# 2_Power.net
KiCad netlist of a schematic drawn in Altium Designer
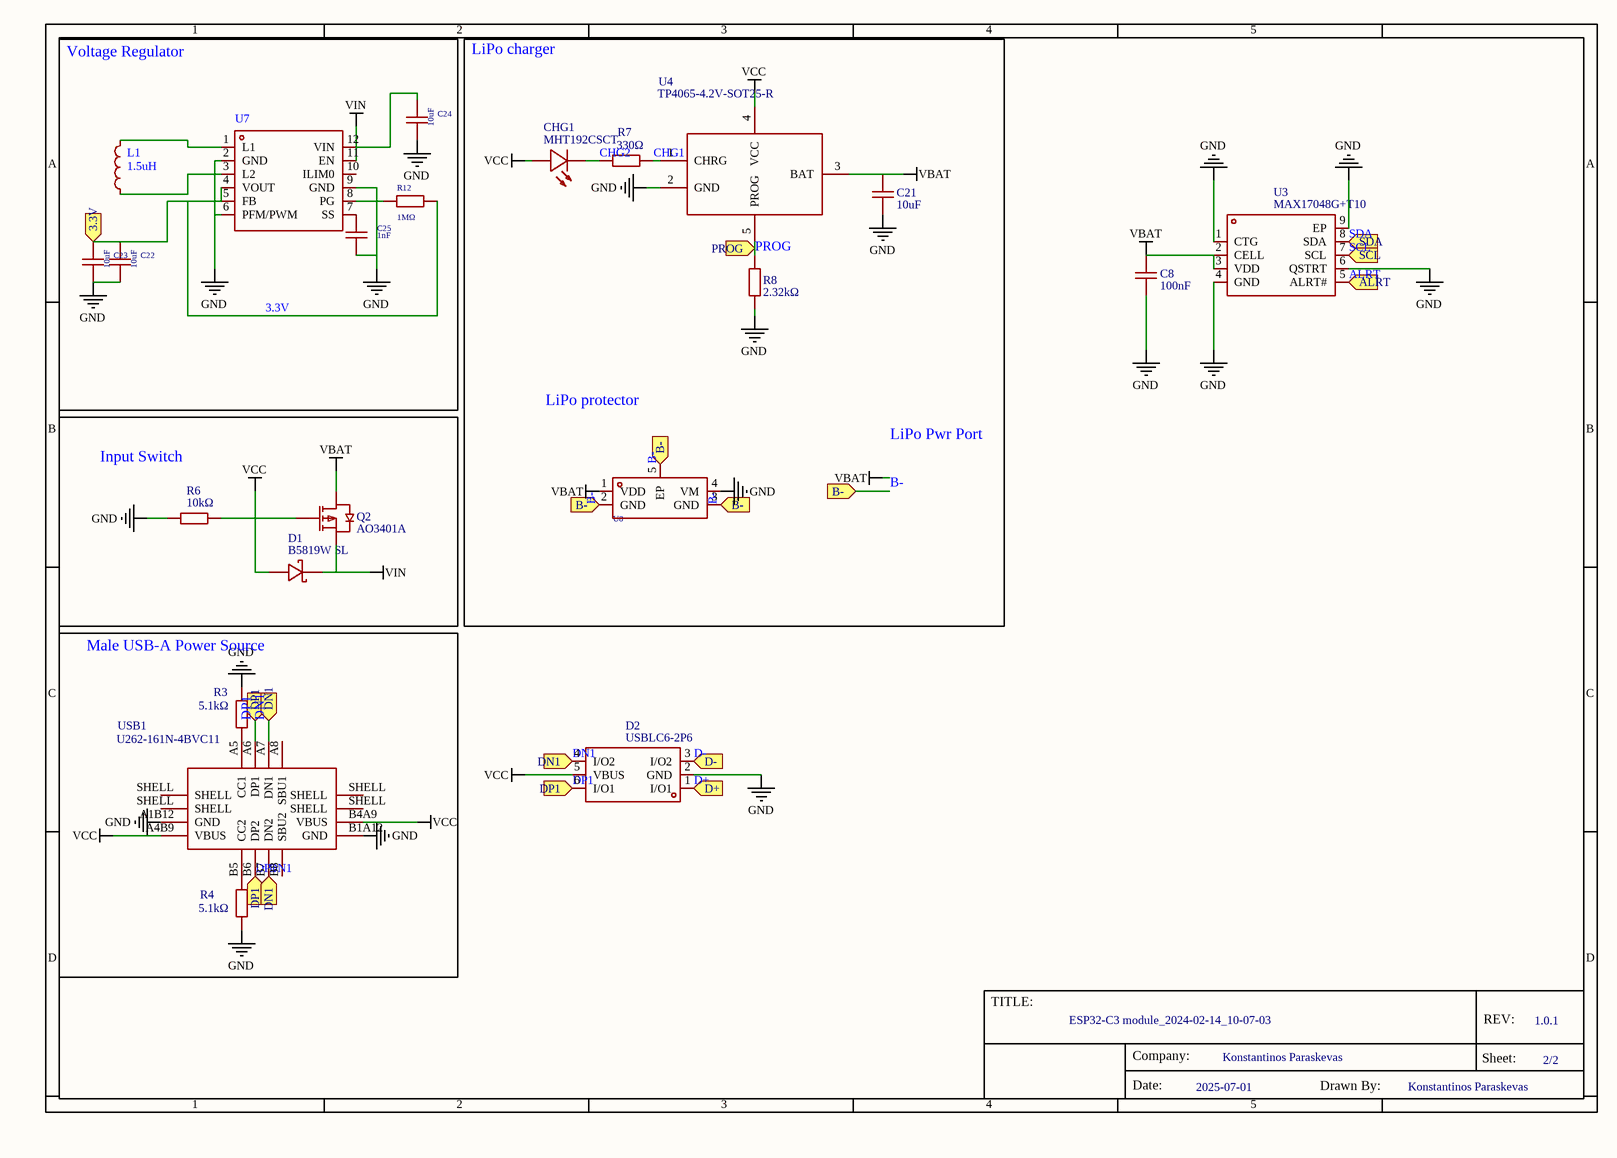
[diagram p0: 2_Power.schdoc]

(export (version "E")
  (design (tool "Eeschema 10.0.6"))
  (components
    (comp (ref "C8")
      (value "100nF")
      (footprint "C0402")
      (fields
        (field (name "MANUFACTURER") "FH(风华)")
        (field (name "MANUFACTURER PART") "0402B104K160NT")
        (field (name "TOLERANCE") "±10%")
      )
      (libsource (lib "altium-import") (part "root_1_0402B104K160NT_"))
    )
    (comp (ref "C21")
      (value "10uF")
      (footprint "C0402")
      (fields
        (field (name "MANUFACTURER") "SAMSUNG(三星)")
        (field (name "MANUFACTURER PART") "CL05A106MQ5NUNC")
        (field (name "TOLERANCE") "±20%")
      )
      (libsource (lib "altium-import") (part "root_1_CL05A106MQ5NUNC_"))
    )
    (comp (ref "C22")
      (value "10uF")
      (footprint "C0402")
      (fields
        (field (name "MANUFACTURER PART") "CL05A106MQ5NUNC")
        (field (name "MANUFACTURER") "SAMSUNG(三星)")
        (field (name "ALTIUM_VALUE") "10uF")
        (field (name "TOLERANCE") "±20%")
      )
      (libsource (lib "altium-import") (part "root_1_CL05A106MQ5NUNC_"))
    )
    (comp (ref "C23")
      (value "10uF")
      (footprint "C0402")
      (fields
        (field (name "MANUFACTURER PART") "CL05A106MQ5NUNC")
        (field (name "MANUFACTURER") "SAMSUNG(三星)")
        (field (name "ALTIUM_VALUE") "10uF")
        (field (name "TOLERANCE") "±20%")
      )
      (libsource (lib "altium-import") (part "root_1_CL05A106MQ5NUNC_"))
    )
    (comp (ref "C24")
      (value "10uF")
      (footprint "C0402")
      (fields
        (field (name "MANUFACTURER PART") "CL05A106MQ5NUNC")
        (field (name "MANUFACTURER") "SAMSUNG(三星)")
        (field (name "ALTIUM_VALUE") "10uF")
        (field (name "TOLERANCE") "±20%")
      )
      (libsource (lib "altium-import") (part "root_1_CL05A106MQ5NUNC_"))
    )
    (comp (ref "C25")
      (value "1nF")
      (footprint "C0402")
      (fields
        (field (name "MANUFACTURER") "YAGEO(国巨)")
        (field (name "MANUFACTURER PART") "CC0402KRX7R9BB102")
        (field (name "ALTIUM_VALUE") "1nF")
        (field (name "TOLERANCE") "±10%")
      )
      (libsource (lib "altium-import") (part "root_1_CC0402KRX7R9BB102_"))
    )
    (comp (ref "CHG1")
      (value "MHT192CSCT")
      (footprint "LED0603-R-RD_ORANGE")
      (fields (field (name "MANUFACTURER") "MEIHUA(美华)"))
      (libsource (lib "altium-import") (part "root_2_MHT192CSCT_"))
    )
    (comp (ref "D1")
      (value "B5819W SL")
      (footprint "SOD-123_L2.7-W1.6-LS3.7-RD-1")
      (fields (field (name "MANUFACTURER") "CJ(江苏长电/长晶)"))
      (libsource (lib "altium-import") (part "root_2_B5819W SL_"))
    )
    (comp (ref "D2")
      (value "USBLC6-2P6")
      (footprint "SOT-666-6_L1.6-W1.2-P0.50-LS1.6-BL")
      (fields (field (name "MANUFACTURER") "TECH PUBLIC(台舟)"))
      (libsource (lib "altium-import") (part "root_2_USBLC6-2P6_"))
    )
    (comp (ref "L1")
      (value "1.5uH")
      (footprint "L0806")
      (fields
        (field (name "MANUFACTURER") "muRata(村田)")
        (field (name "MANUFACTURER PART") "DFE201610E-1R5M=P2")
        (field (name "ALTIUM_VALUE") "1.5uH")
        (field (name "TOLERANCE") "±20%")
      )
      (libsource (lib "altium-import") (part "root_1_DFE201610E-1R5M=P2_"))
    )
    (comp (ref "Q2")
      (value "AO3401A")
      (footprint "SOT-23_L2.9-W1.3-P1.90-LS2.4-BR")
      (fields (field (name "MANUFACTURER") "AOS"))
      (libsource (lib "altium-import") (part "root_0_AO3401A_C15127_"))
    )
    (comp (ref "R3")
      (value "5.1kΩ")
      (footprint "R0402")
      (fields
        (field (name "MANUFACTURER") "UNI-ROYAL(厚声)")
        (field (name "MANUFACTURER PART") "0402WGJ0512TCE")
        (field (name "TOLERANCE") "±5%")
      )
      (libsource (lib "altium-import") (part "root_1_0402WGJ0512TCE_"))
    )
    (comp (ref "R4")
      (value "5.1kΩ")
      (footprint "R0402")
      (fields
        (field (name "MANUFACTURER") "UNI-ROYAL(厚声)")
        (field (name "MANUFACTURER PART") "0402WGJ0512TCE")
        (field (name "TOLERANCE") "±5%")
      )
      (libsource (lib "altium-import") (part "root_1_0402WGJ0512TCE_"))
    )
    (comp (ref "R6")
      (value "10kΩ")
      (footprint "R0402")
      (fields
        (field (name "MANUFACTURER") "大毅科技")
        (field (name "MANUFACTURER PART") "RMS04FT1002")
        (field (name "TOLERANCE") "±1%")
      )
      (libsource (lib "altium-import") (part "root_0_RMS04FT1002_"))
    )
    (comp (ref "R7")
      (value "330Ω")
      (footprint "R0402")
      (fields
        (field (name "MANUFACTURER") "UNI-ROYAL(厚声)")
        (field (name "MANUFACTURER PART") "0402WGF3300TCE")
        (field (name "TOLERANCE") "±1%")
      )
      (libsource (lib "altium-import") (part "root_0_0402WGF3300TCE_"))
    )
    (comp (ref "R8")
      (value "2.32kΩ")
      (footprint "R0402")
      (fields
        (field (name "MANUFACTURER") "Walsin(华新科)")
        (field (name "MANUFACTURER PART") "WR04X2321FTL")
        (field (name "TOLERANCE") "±1%")
      )
      (libsource (lib "altium-import") (part "root_1_WR04X2321FTL_"))
    )
    (comp (ref "R12")
      (value "1MΩ")
      (footprint "R0402")
      (fields
        (field (name "MANUFACTURER") "UNI-ROYAL(厚声)")
        (field (name "MANUFACTURER PART") "0402WGF1004TCE")
        (field (name "ALTIUM_VALUE") "1MΩ")
        (field (name "TOLERANCE") "±1%")
      )
      (libsource (lib "altium-import") (part "root_0_0402WGF1004TCE_"))
    )
    (comp (ref "U3")
      (value "MAX17048G+T10")
      (footprint "DFN-8_L2.0-W2.0-P0.50-BL-EP")
      (fields (field (name "MANUFACTURER") "ADI(亚德诺)/MAXIM(美信)"))
      (libsource (lib "altium-import") (part "root_0_MAX17048G+T10_"))
    )
    (comp (ref "U4")
      (value "TP4065-4.2V-SOT25-R")
      (footprint "SOT-23-5_L3.0-W1.7-P0.95-LS2.8-BR")
      (fields (field (name "MANUFACTURER") "TOPPOWER(南京拓微)"))
      (libsource (lib "altium-import") (part "root_0_TP4065-4.2V-SOT25-R_"))
    )
    (comp (ref "U7")
      (value "TPS63051RMWR")
      (footprint "QFN-12_L2.5-W2.5-P0.50-TL")
      (fields (field (name "MANUFACTURER") "TI(德州仪器)"))
      (libsource (lib "altium-import") (part "root_0_TPS63051RMWR_"))
    )
    (comp (ref "U8")
      (value "AP6683")
      (footprint "DFN-4_L1.0-W1.0-P0.65-BL-EP")
      (fields (field (name "MANUFACTURER") "ALLPOWER(铨力)"))
      (libsource (lib "altium-import") (part "root_0_AP6683_"))
    )
    (comp (ref "USB1")
      (value "U262-161N-4BVC11")
      (footprint "USB-3.1-SMD_U262-161N-4BVC11")
      (fields (field (name "MANUFACTURER") "XKB Connectivity(中国星坤)"))
      (libsource (lib "altium-import") (part "root_0_U262-161N-4BVC11_"))
    )
  )
  (nets
    (net (code "1") (name "/3.3V") (class "Default")
      (node (ref "C22") (pin "2") (pinfunction "2_2") (pintype "passive"))
      (node (ref "C23") (pin "2") (pinfunction "2_2") (pintype "passive"))
      (node (ref "R12") (pin "2") (pinfunction "2_2") (pintype "passive"))
      (node (ref "U7") (pin "4") (pinfunction "VOUT_4") (pintype "passive"))
      (node (ref "U7") (pin "5") (pinfunction "FB_5") (pintype "passive"))
    )
    (net (code "2") (name "/ALRT") (class "Default")
      (node (ref "U3") (pin "5") (pinfunction "ALRT#_5") (pintype "passive"))
    )
    (net (code "3") (name "/B-") (class "Default")
      (node (ref "U8") (pin "2") (pinfunction "GND_2") (pintype "passive"))
      (node (ref "U8") (pin "3") (pinfunction "GND_3") (pintype "passive"))
      (node (ref "U8") (pin "5") (pinfunction "EP_5") (pintype "passive"))
    )
    (net (code "4") (name "/CHG1") (class "Default")
      (node (ref "R7") (pin "2") (pinfunction "2_2") (pintype "passive"))
      (node (ref "U4") (pin "1") (pinfunction "CHRG_1") (pintype "passive"))
    )
    (net (code "5") (name "/CHG2") (class "Default")
      (node (ref "CHG1") (pin "2") (pinfunction "K_2") (pintype "passive"))
      (node (ref "R7") (pin "1") (pinfunction "1_1") (pintype "passive"))
    )
    (net (code "6") (name "/D+") (class "Default")
      (node (ref "D2") (pin "1") (pinfunction "I/O1_1") (pintype "passive"))
    )
    (net (code "7") (name "/D-") (class "Default")
      (node (ref "D2") (pin "3") (pinfunction "I/O2_3") (pintype "passive"))
    )
    (net (code "8") (name "/DN1") (class "Default")
      (node (ref "D2") (pin "4") (pinfunction "I/O2_4") (pintype "passive"))
      (node (ref "USB1") (pin "A7") (pinfunction "DN1_A7") (pintype "passive"))
      (node (ref "USB1") (pin "B7") (pinfunction "DN2_B7") (pintype "passive"))
    )
    (net (code "9") (name "/DP1") (class "Default")
      (node (ref "D2") (pin "6") (pinfunction "I/O1_6") (pintype "passive"))
      (node (ref "USB1") (pin "A6") (pinfunction "DP1_A6") (pintype "passive"))
      (node (ref "USB1") (pin "B6") (pinfunction "DP2_B6") (pintype "passive"))
    )
    (net (code "10") (name "/PROG") (class "Default")
      (node (ref "R8") (pin "2") (pinfunction "2_2") (pintype "passive"))
      (node (ref "U4") (pin "5") (pinfunction "PROG_5") (pintype "passive"))
    )
    (net (code "11") (name "/SCL") (class "Default")
      (node (ref "U3") (pin "7") (pinfunction "SCL_7") (pintype "passive"))
    )
    (net (code "12") (name "/SDA") (class "Default")
      (node (ref "U3") (pin "8") (pinfunction "SDA_8") (pintype "passive"))
    )
    (net (code "13") (name "GND") (class "Default")
      (node (ref "C21") (pin "1") (pinfunction "1_1") (pintype "passive"))
      (node (ref "C22") (pin "1") (pinfunction "1_1") (pintype "passive"))
      (node (ref "C23") (pin "1") (pinfunction "1_1") (pintype "passive"))
      (node (ref "C24") (pin "1") (pinfunction "1_1") (pintype "passive"))
      (node (ref "C25") (pin "1") (pinfunction "1_1") (pintype "passive"))
      (node (ref "C8") (pin "1") (pinfunction "1_1") (pintype "passive"))
      (node (ref "D2") (pin "2") (pinfunction "GND_2") (pintype "passive"))
      (node (ref "R3") (pin "2") (pinfunction "2_2") (pintype "passive"))
      (node (ref "R4") (pin "1") (pinfunction "1_1") (pintype "passive"))
      (node (ref "R6") (pin "1") (pinfunction "1_1") (pintype "passive"))
      (node (ref "R8") (pin "1") (pinfunction "1_1") (pintype "passive"))
      (node (ref "U3") (pin "1") (pinfunction "CTG_1") (pintype "passive"))
      (node (ref "U3") (pin "4") (pinfunction "GND_4") (pintype "passive"))
      (node (ref "U3") (pin "6") (pinfunction "QSTRT_6") (pintype "passive"))
      (node (ref "U3") (pin "9") (pinfunction "EP_9") (pintype "passive"))
      (node (ref "U4") (pin "2") (pinfunction "GND_2") (pintype "passive"))
      (node (ref "U7") (pin "2") (pinfunction "GND_2") (pintype "passive"))
      (node (ref "U7") (pin "6") (pinfunction "PFM/PWM_6") (pintype "passive"))
      (node (ref "U7") (pin "9") (pinfunction "GND_9") (pintype "passive"))
      (node (ref "U8") (pin "4") (pinfunction "VM_4") (pintype "passive"))
      (node (ref "USB1") (pin "A1B12") (pinfunction "GND_A1B12") (pintype "passive"))
      (node (ref "USB1") (pin "B1A12") (pinfunction "GND_B1A12") (pintype "passive"))
    )
    (net (code "14") (name "Net-(U7-L1)") (class "Default")
      (node (ref "L1") (pin "2") (pinfunction "2_2") (pintype "passive"))
      (node (ref "U7") (pin "1") (pinfunction "L1_1") (pintype "passive"))
    )
    (net (code "15") (name "Net-(U7-L2)") (class "Default")
      (node (ref "L1") (pin "1") (pinfunction "1_1") (pintype "passive"))
      (node (ref "U7") (pin "3") (pinfunction "L2_3") (pintype "passive"))
    )
    (net (code "16") (name "Net-(U7-PG)") (class "Default")
      (node (ref "R12") (pin "1") (pinfunction "1_1") (pintype "passive"))
      (node (ref "U7") (pin "8") (pinfunction "PG_8") (pintype "passive"))
    )
    (net (code "17") (name "Net-(U7-SS)") (class "Default")
      (node (ref "C25") (pin "2") (pinfunction "2_2") (pintype "passive"))
      (node (ref "U7") (pin "7") (pinfunction "SS_7") (pintype "passive"))
    )
    (net (code "18") (name "Net-(USB1-CC1)") (class "Default")
      (node (ref "R3") (pin "1") (pinfunction "1_1") (pintype "passive"))
      (node (ref "USB1") (pin "A5") (pinfunction "CC1_A5") (pintype "passive"))
    )
    (net (code "19") (name "Net-(USB1-CC2)") (class "Default")
      (node (ref "R4") (pin "2") (pinfunction "2_2") (pintype "passive"))
      (node (ref "USB1") (pin "B5") (pinfunction "CC2_B5") (pintype "passive"))
    )
    (net (code "20") (name "VBAT") (class "Default")
      (node (ref "C21") (pin "2") (pinfunction "2_2") (pintype "passive"))
      (node (ref "C8") (pin "2") (pinfunction "2_2") (pintype "passive"))
      (node (ref "Q2") (pin "3") (pinfunction "D_3") (pintype "passive"))
      (node (ref "U3") (pin "2") (pinfunction "CELL_2") (pintype "passive"))
      (node (ref "U3") (pin "3") (pinfunction "VDD_3") (pintype "passive"))
      (node (ref "U4") (pin "3") (pinfunction "BAT_3") (pintype "passive"))
      (node (ref "U8") (pin "1") (pinfunction "VDD_1") (pintype "passive"))
    )
    (net (code "21") (name "VCC") (class "Default")
      (node (ref "CHG1") (pin "1") (pinfunction "A_1") (pintype "passive"))
      (node (ref "D1") (pin "2") (pinfunction "+_2") (pintype "passive"))
      (node (ref "D2") (pin "5") (pinfunction "VBUS_5") (pintype "passive"))
      (node (ref "Q2") (pin "1") (pinfunction "G_1") (pintype "passive"))
      (node (ref "R6") (pin "2") (pinfunction "2_2") (pintype "passive"))
      (node (ref "U4") (pin "4") (pinfunction "VCC_4") (pintype "passive"))
      (node (ref "USB1") (pin "A4B9") (pinfunction "VBUS_A4B9") (pintype "passive"))
      (node (ref "USB1") (pin "B4A9") (pinfunction "VBUS_B4A9") (pintype "passive"))
    )
    (net (code "22") (name "VIN") (class "Default")
      (node (ref "C24") (pin "2") (pinfunction "2_2") (pintype "passive"))
      (node (ref "D1") (pin "1") (pinfunction "-_1") (pintype "passive"))
      (node (ref "Q2") (pin "2") (pinfunction "S_2") (pintype "passive"))
      (node (ref "U7") (pin "11") (pinfunction "EN_11") (pintype "passive"))
      (node (ref "U7") (pin "12") (pinfunction "VIN_12") (pintype "passive"))
    )
    (net (code "23") (name "unconnected-(U7-ILIM0-Pad10)") (class "Default")
      (node (ref "U7") (pin "10") (pinfunction "ILIM0_10") (pintype "passive"))
    )
    (net (code "24") (name "unconnected-(USB1-PadSHELL)") (class "Default")
      (node (ref "USB1") (pin "SHELL") (pinfunction "SHELL_SHELL") (pintype "passive"))
    )
    (net (code "25") (name "unconnected-(USB1-PadSHELL)_1") (class "Default")
      (node (ref "USB1") (pin "SHELL") (pinfunction "SHELL_SHELL") (pintype "passive"))
    )
    (net (code "26") (name "unconnected-(USB1-PadSHELL)_2") (class "Default")
      (node (ref "USB1") (pin "SHELL") (pinfunction "SHELL_SHELL") (pintype "passive"))
    )
    (net (code "27") (name "unconnected-(USB1-PadSHELL)_3") (class "Default")
      (node (ref "USB1") (pin "SHELL") (pinfunction "SHELL_SHELL") (pintype "passive"))
    )
    (net (code "28") (name "unconnected-(USB1-SBU1-PadA8)") (class "Default")
      (node (ref "USB1") (pin "A8") (pinfunction "SBU1_A8") (pintype "passive"))
    )
    (net (code "29") (name "unconnected-(USB1-SBU2-PadB8)") (class "Default")
      (node (ref "USB1") (pin "B8") (pinfunction "SBU2_B8") (pintype "passive"))
    )
  )
)
